# Sheet1.net
KiCad netlist of a schematic drawn in Altium Designer
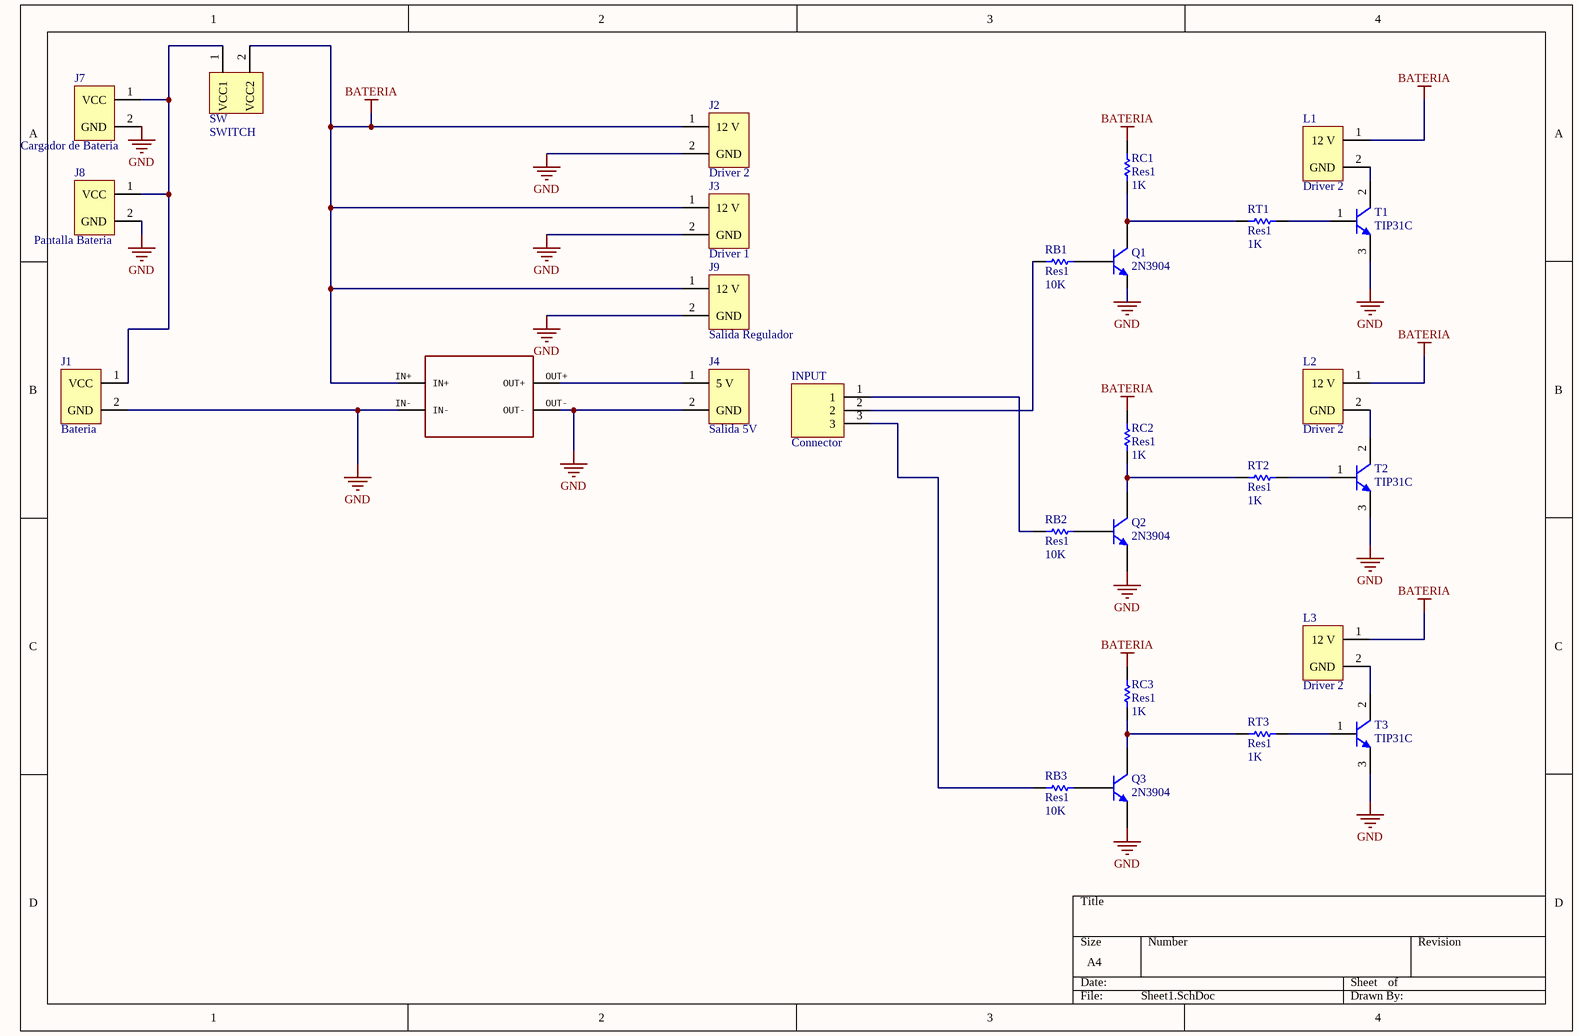
[diagram p0: Sheet1.SchDoc]

(export (version "E")
  (design (tool "Eeschema 10.0.6"))
  (components
    (comp (ref "INPUT")
      (value "Connector")
      (footprint "1x3x2.54 Pin Header TH V")
      (libsource (lib "CARO") (part "Header 1x3"))
    )
    (comp (ref "J1") (value "Bateria") (footprint "CONN2") (libsource (lib "Schlib1") (part "Bornera")))
    (comp (ref "J2") (value "Driver 2") (footprint "CONN2") (libsource (lib "") (part "Bornera_2")))
    (comp (ref "J3") (value "Driver 1") (footprint "CONN2") (libsource (lib "") (part "Bornera_2")))
    (comp (ref "J4") (value "Salida 5V") (footprint "CONN2") (libsource (lib "") (part "Bornera_3")))
    (comp (ref "J7")
      (value "Cargador de Bateria")
      (footprint "CONN2")
      (libsource (lib "Schlib1") (part "Bornera"))
    )
    (comp (ref "J8")
      (value "Pantalla Bateria")
      (footprint "CONN2")
      (libsource (lib "Schlib1") (part "Bornera"))
    )
    (comp (ref "J9") (value "Salida Regulador") (footprint "CONN2") (libsource (lib "") (part "Bornera_2")))
    (comp (ref "L1") (value "Driver 2") (footprint "CONN2") (libsource (lib "Schlib1") (part "Bornera")))
    (comp (ref "L2") (value "Driver 2") (footprint "CONN2") (libsource (lib "Schlib1") (part "Bornera")))
    (comp (ref "L3") (value "Driver 2") (footprint "CONN2") (libsource (lib "Schlib1") (part "Bornera")))
    (comp (ref "Q1")
      (value "2N3904")
      (footprint "TO-92A")
      (description "NPN General Purpose Amplifier")
      (fields (field (name "PUBLISHER") "Altium Limited"))
      (libsource (lib "Miscellaneous Devices") (part "2N3904"))
    )
    (comp (ref "Q2")
      (value "2N3904")
      (footprint "TO-92A")
      (description "NPN General Purpose Amplifier")
      (fields (field (name "PUBLISHER") "Altium Limited"))
      (libsource (lib "Miscellaneous Devices") (part "2N3904"))
    )
    (comp (ref "Q3")
      (value "2N3904")
      (footprint "TO-92A")
      (description "NPN General Purpose Amplifier")
      (fields (field (name "PUBLISHER") "Altium Limited"))
      (libsource (lib "Miscellaneous Devices") (part "2N3904"))
    )
    (comp (ref "RB1")
      (value "Res1")
      (footprint "AXIAL-0.3")
      (description "Resistor")
      (fields (field (name "ALTIUM_VALUE") "10K") (field (name "PUBLISHER") "Altium Limited"))
      (libsource (lib "Miscellaneous Devices") (part "Res1"))
    )
    (comp (ref "RB2")
      (value "Res1")
      (footprint "AXIAL-0.3")
      (description "Resistor")
      (fields (field (name "ALTIUM_VALUE") "10K") (field (name "PUBLISHER") "Altium Limited"))
      (libsource (lib "Miscellaneous Devices") (part "Res1"))
    )
    (comp (ref "RB3")
      (value "Res1")
      (footprint "AXIAL-0.3")
      (description "Resistor")
      (fields (field (name "ALTIUM_VALUE") "10K") (field (name "PUBLISHER") "Altium Limited"))
      (libsource (lib "Miscellaneous Devices") (part "Res1"))
    )
    (comp (ref "RC1")
      (value "Res1")
      (footprint "AXIAL-0.3")
      (description "Resistor")
      (fields (field (name "ALTIUM_VALUE") "1K") (field (name "PUBLISHER") "Altium Limited"))
      (libsource (lib "Miscellaneous Devices") (part "Res1"))
    )
    (comp (ref "RC2")
      (value "Res1")
      (footprint "AXIAL-0.3")
      (description "Resistor")
      (fields (field (name "ALTIUM_VALUE") "1K") (field (name "PUBLISHER") "Altium Limited"))
      (libsource (lib "Miscellaneous Devices") (part "Res1"))
    )
    (comp (ref "RC3")
      (value "Res1")
      (footprint "AXIAL-0.3")
      (description "Resistor")
      (fields (field (name "ALTIUM_VALUE") "1K") (field (name "PUBLISHER") "Altium Limited"))
      (libsource (lib "Miscellaneous Devices") (part "Res1"))
    )
    (comp (ref "REG1")
      (value "Voltage regulator IN: 7-35V OUT: ADJ")
      (footprint "CP8-ADJ")
      (fields (field (name "LIBRARYNAME") "userlib"))
      (libsource (lib "Integrated_Library1") (part "CP8-ADJ"))
    )
    (comp (ref "RT1")
      (value "Res1")
      (footprint "AXIAL-0.3")
      (description "Resistor")
      (fields (field (name "ALTIUM_VALUE") "1K") (field (name "PUBLISHER") "Altium Limited"))
      (libsource (lib "Miscellaneous Devices") (part "Res1"))
    )
    (comp (ref "RT2")
      (value "Res1")
      (footprint "AXIAL-0.3")
      (description "Resistor")
      (fields (field (name "ALTIUM_VALUE") "1K") (field (name "PUBLISHER") "Altium Limited"))
      (libsource (lib "Miscellaneous Devices") (part "Res1"))
    )
    (comp (ref "RT3")
      (value "Res1")
      (footprint "AXIAL-0.3")
      (description "Resistor")
      (fields (field (name "ALTIUM_VALUE") "1K") (field (name "PUBLISHER") "Altium Limited"))
      (libsource (lib "Miscellaneous Devices") (part "Res1"))
    )
    (comp (ref "SW") (value "SWITCH") (footprint "CONN2") (libsource (lib "") (part "Bornera_1")))
    (comp (ref "T1")
      (value "TIP31C")
      (footprint "ONSC-TO-220-3-221A-09")
      (description "Complementary Silicon Plastic Power Transistor, 3-Pin TO-220, Tube")
      (fields (field (name "MANUFACTURER") "On Semiconductor"))
      (libsource (lib "Altium Content Vault") (part "ONSC-NPN-B1C2E3-3_C"))
    )
    (comp (ref "T2")
      (value "TIP31C")
      (footprint "ONSC-TO-220-3-221A-09")
      (description "Complementary Silicon Plastic Power Transistor, 3-Pin TO-220, Tube")
      (fields (field (name "MANUFACTURER") "On Semiconductor"))
      (libsource (lib "Altium Content Vault") (part "ONSC-NPN-B1C2E3-3_C"))
    )
    (comp (ref "T3")
      (value "TIP31C")
      (footprint "ONSC-TO-220-3-221A-09")
      (description "Complementary Silicon Plastic Power Transistor, 3-Pin TO-220, Tube")
      (fields (field (name "MANUFACTURER") "On Semiconductor"))
      (libsource (lib "Altium Content Vault") (part "ONSC-NPN-B1C2E3-3_C"))
    )
  )
  (nets
    (net (code "1") (name "BATERIA") (class "Default")
      (node (ref "J2") (pin "1") (pinfunction "12_V_1") (pintype "passive"))
      (node (ref "J3") (pin "1") (pinfunction "12_V_1") (pintype "passive"))
      (node (ref "J9") (pin "1") (pinfunction "12_V_1") (pintype "passive"))
      (node (ref "L1") (pin "1") (pinfunction "VCC_1") (pintype "passive"))
      (node (ref "L2") (pin "1") (pinfunction "VCC_1") (pintype "passive"))
      (node (ref "L3") (pin "1") (pinfunction "VCC_1") (pintype "passive"))
      (node (ref "RC1") (pin "2") (pinfunction "2_2") (pintype "passive"))
      (node (ref "RC2") (pin "2") (pinfunction "2_2") (pintype "passive"))
      (node (ref "RC3") (pin "2") (pinfunction "2_2") (pintype "passive"))
      (node (ref "REG1") (pin "IN+") (pinfunction "IN+_IN+") (pintype "passive"))
      (node (ref "SW") (pin "2") (pinfunction "VCC2_2") (pintype "passive"))
    )
    (net (code "2") (name "GND") (class "Default")
      (node (ref "J1") (pin "2") (pinfunction "GND_2") (pintype "passive"))
      (node (ref "J2") (pin "2") (pinfunction "GND_2") (pintype "passive"))
      (node (ref "J3") (pin "2") (pinfunction "GND_2") (pintype "passive"))
      (node (ref "J4") (pin "2") (pinfunction "GND_2") (pintype "passive"))
      (node (ref "J7") (pin "2") (pinfunction "GND_2") (pintype "passive"))
      (node (ref "J8") (pin "2") (pinfunction "GND_2") (pintype "passive"))
      (node (ref "J9") (pin "2") (pinfunction "GND_2") (pintype "passive"))
      (node (ref "Q1") (pin "1") (pinfunction "E_1") (pintype "passive"))
      (node (ref "Q2") (pin "1") (pinfunction "E_1") (pintype "passive"))
      (node (ref "Q3") (pin "1") (pinfunction "E_1") (pintype "passive"))
      (node (ref "REG1") (pin "IN-") (pinfunction "IN-_IN-") (pintype "passive"))
      (node (ref "REG1") (pin "OUT-") (pinfunction "OUT-_OUT-") (pintype "passive"))
      (node (ref "T1") (pin "3") (pinfunction "E_3") (pintype "passive"))
      (node (ref "T2") (pin "3") (pinfunction "E_3") (pintype "passive"))
      (node (ref "T3") (pin "3") (pinfunction "E_3") (pintype "passive"))
    )
    (net (code "3") (name "Net-(INPUT-Pad1)") (class "Default")
      (node (ref "INPUT") (pin "1") (pinfunction "1_1") (pintype "passive"))
      (node (ref "RB2") (pin "1") (pinfunction "1_1") (pintype "passive"))
    )
    (net (code "4") (name "Net-(INPUT-Pad2)") (class "Default")
      (node (ref "INPUT") (pin "2") (pinfunction "2_2") (pintype "passive"))
      (node (ref "RB1") (pin "1") (pinfunction "1_1") (pintype "passive"))
    )
    (net (code "5") (name "Net-(INPUT-Pad3)") (class "Default")
      (node (ref "INPUT") (pin "3") (pinfunction "3_3") (pintype "passive"))
      (node (ref "RB3") (pin "1") (pinfunction "1_1") (pintype "passive"))
    )
    (net (code "6") (name "Net-(J1-VCC)") (class "Default")
      (node (ref "J1") (pin "1") (pinfunction "VCC_1") (pintype "passive"))
      (node (ref "J7") (pin "1") (pinfunction "VCC_1") (pintype "passive"))
      (node (ref "J8") (pin "1") (pinfunction "VCC_1") (pintype "passive"))
      (node (ref "SW") (pin "1") (pinfunction "VCC1_1") (pintype "passive"))
    )
    (net (code "7") (name "Net-(J4-5_V)") (class "Default")
      (node (ref "J4") (pin "1") (pinfunction "5_V_1") (pintype "passive"))
      (node (ref "REG1") (pin "OUT+") (pinfunction "OUT+_OUT+") (pintype "passive"))
    )
    (net (code "8") (name "Net-(L1-GND)") (class "Default")
      (node (ref "L1") (pin "2") (pinfunction "GND_2") (pintype "passive"))
      (node (ref "T1") (pin "2") (pinfunction "C_2") (pintype "passive"))
    )
    (net (code "9") (name "Net-(L2-GND)") (class "Default")
      (node (ref "L2") (pin "2") (pinfunction "GND_2") (pintype "passive"))
      (node (ref "T2") (pin "2") (pinfunction "C_2") (pintype "passive"))
    )
    (net (code "10") (name "Net-(L3-GND)") (class "Default")
      (node (ref "L3") (pin "2") (pinfunction "GND_2") (pintype "passive"))
      (node (ref "T3") (pin "2") (pinfunction "C_2") (pintype "passive"))
    )
    (net (code "11") (name "Net-(Q1-B)") (class "Default")
      (node (ref "Q1") (pin "2") (pinfunction "B_2") (pintype "passive"))
      (node (ref "RB1") (pin "2") (pinfunction "2_2") (pintype "passive"))
    )
    (net (code "12") (name "Net-(Q1-C)") (class "Default")
      (node (ref "Q1") (pin "3") (pinfunction "C_3") (pintype "passive"))
      (node (ref "RC1") (pin "1") (pinfunction "1_1") (pintype "passive"))
      (node (ref "RT1") (pin "1") (pinfunction "1_1") (pintype "passive"))
    )
    (net (code "13") (name "Net-(Q2-B)") (class "Default")
      (node (ref "Q2") (pin "2") (pinfunction "B_2") (pintype "passive"))
      (node (ref "RB2") (pin "2") (pinfunction "2_2") (pintype "passive"))
    )
    (net (code "14") (name "Net-(Q2-C)") (class "Default")
      (node (ref "Q2") (pin "3") (pinfunction "C_3") (pintype "passive"))
      (node (ref "RC2") (pin "1") (pinfunction "1_1") (pintype "passive"))
      (node (ref "RT2") (pin "1") (pinfunction "1_1") (pintype "passive"))
    )
    (net (code "15") (name "Net-(Q3-B)") (class "Default")
      (node (ref "Q3") (pin "2") (pinfunction "B_2") (pintype "passive"))
      (node (ref "RB3") (pin "2") (pinfunction "2_2") (pintype "passive"))
    )
    (net (code "16") (name "Net-(Q3-C)") (class "Default")
      (node (ref "Q3") (pin "3") (pinfunction "C_3") (pintype "passive"))
      (node (ref "RC3") (pin "1") (pinfunction "1_1") (pintype "passive"))
      (node (ref "RT3") (pin "1") (pinfunction "1_1") (pintype "passive"))
    )
    (net (code "17") (name "Net-(T1-B)") (class "Default")
      (node (ref "RT1") (pin "2") (pinfunction "2_2") (pintype "passive"))
      (node (ref "T1") (pin "1") (pinfunction "B_1") (pintype "passive"))
    )
    (net (code "18") (name "Net-(T2-B)") (class "Default")
      (node (ref "RT2") (pin "2") (pinfunction "2_2") (pintype "passive"))
      (node (ref "T2") (pin "1") (pinfunction "B_1") (pintype "passive"))
    )
    (net (code "19") (name "Net-(T3-B)") (class "Default")
      (node (ref "RT3") (pin "2") (pinfunction "2_2") (pintype "passive"))
      (node (ref "T3") (pin "1") (pinfunction "B_1") (pintype "passive"))
    )
  )
)
